# MainModule.net
KiCad netlist of a schematic drawn in EAGLE
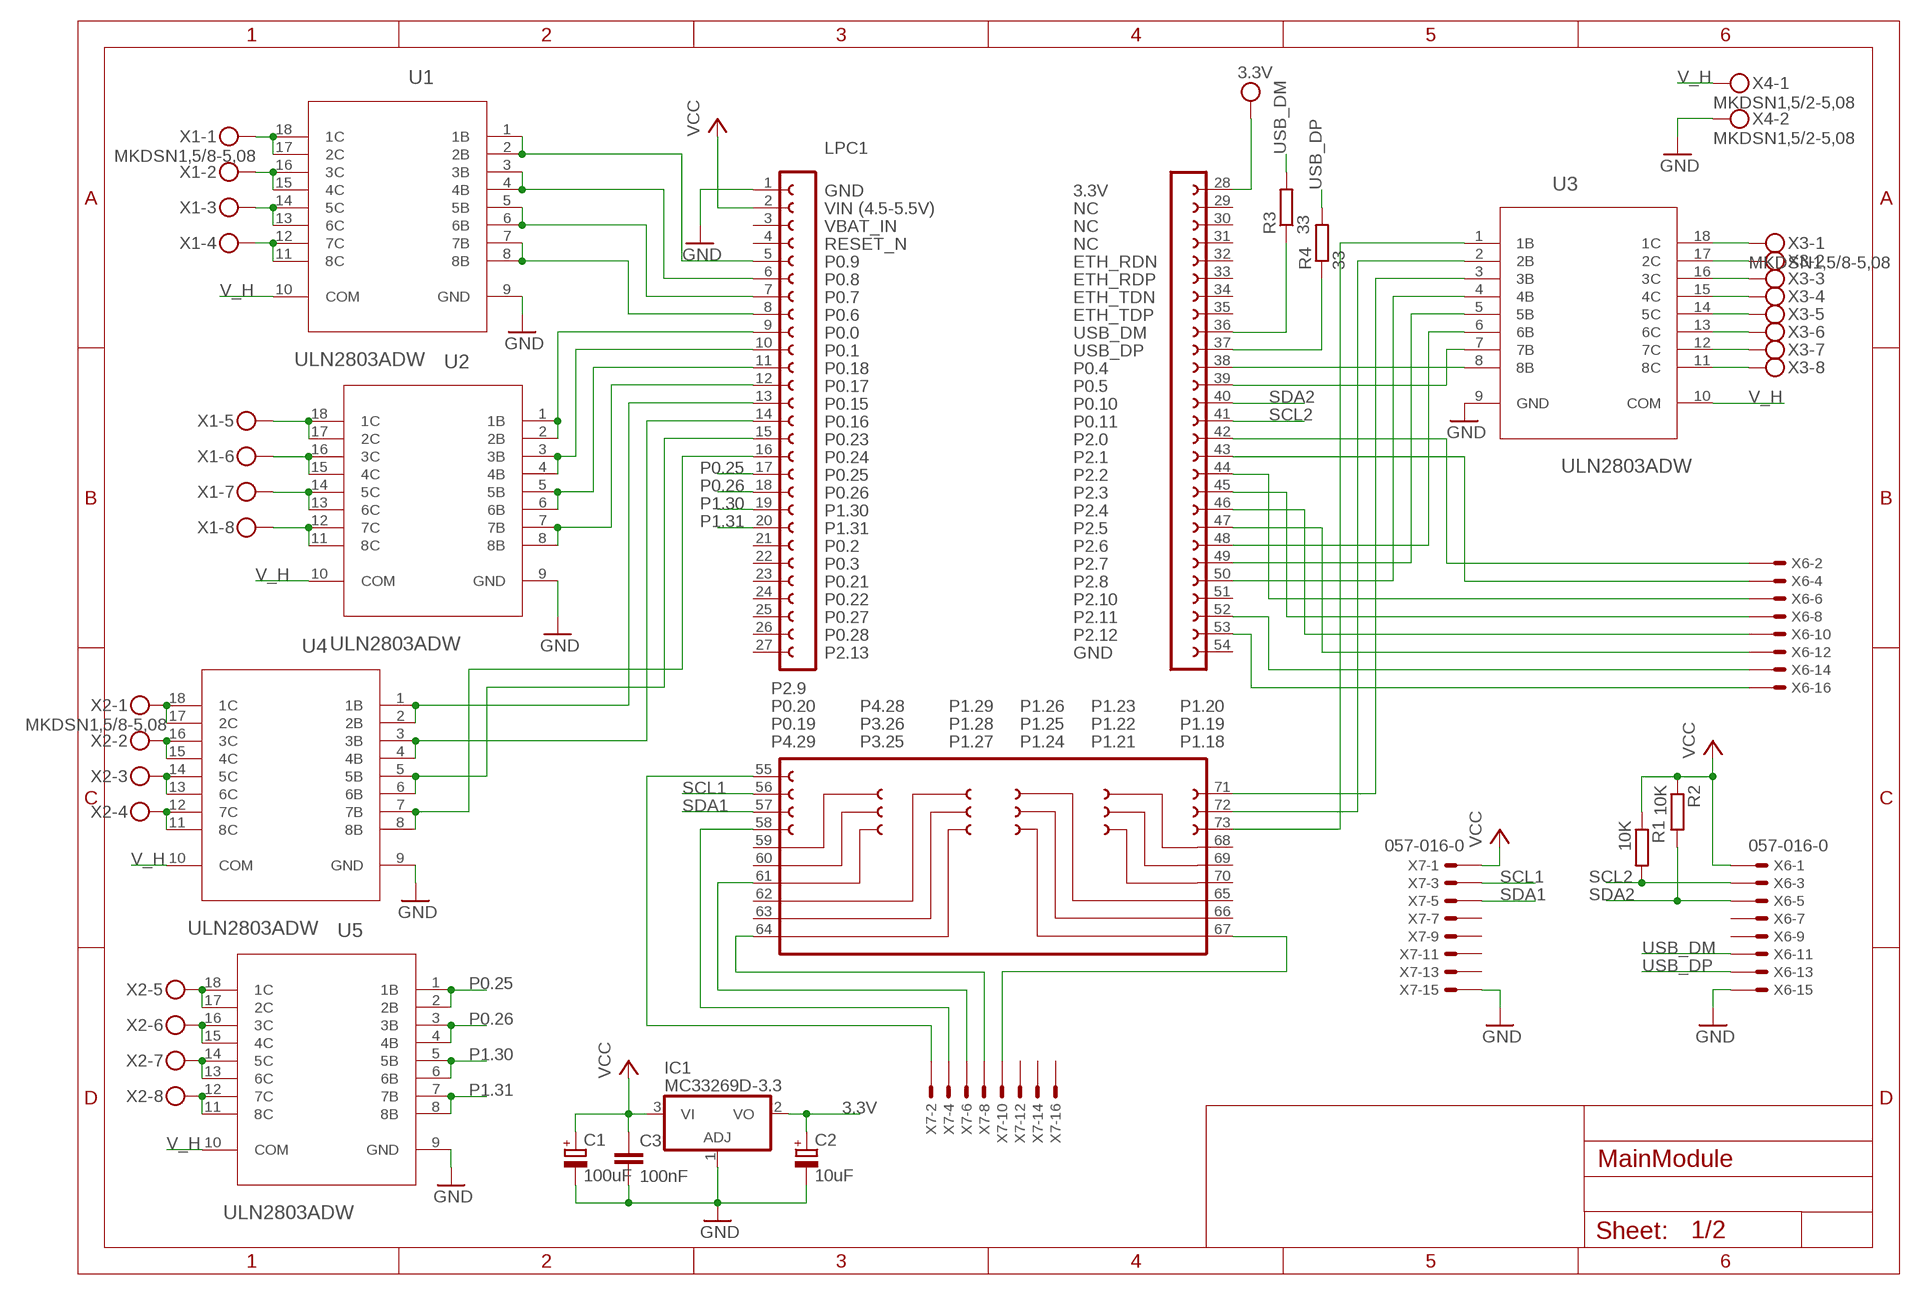
[diagram p0: schematic, sheet 1]
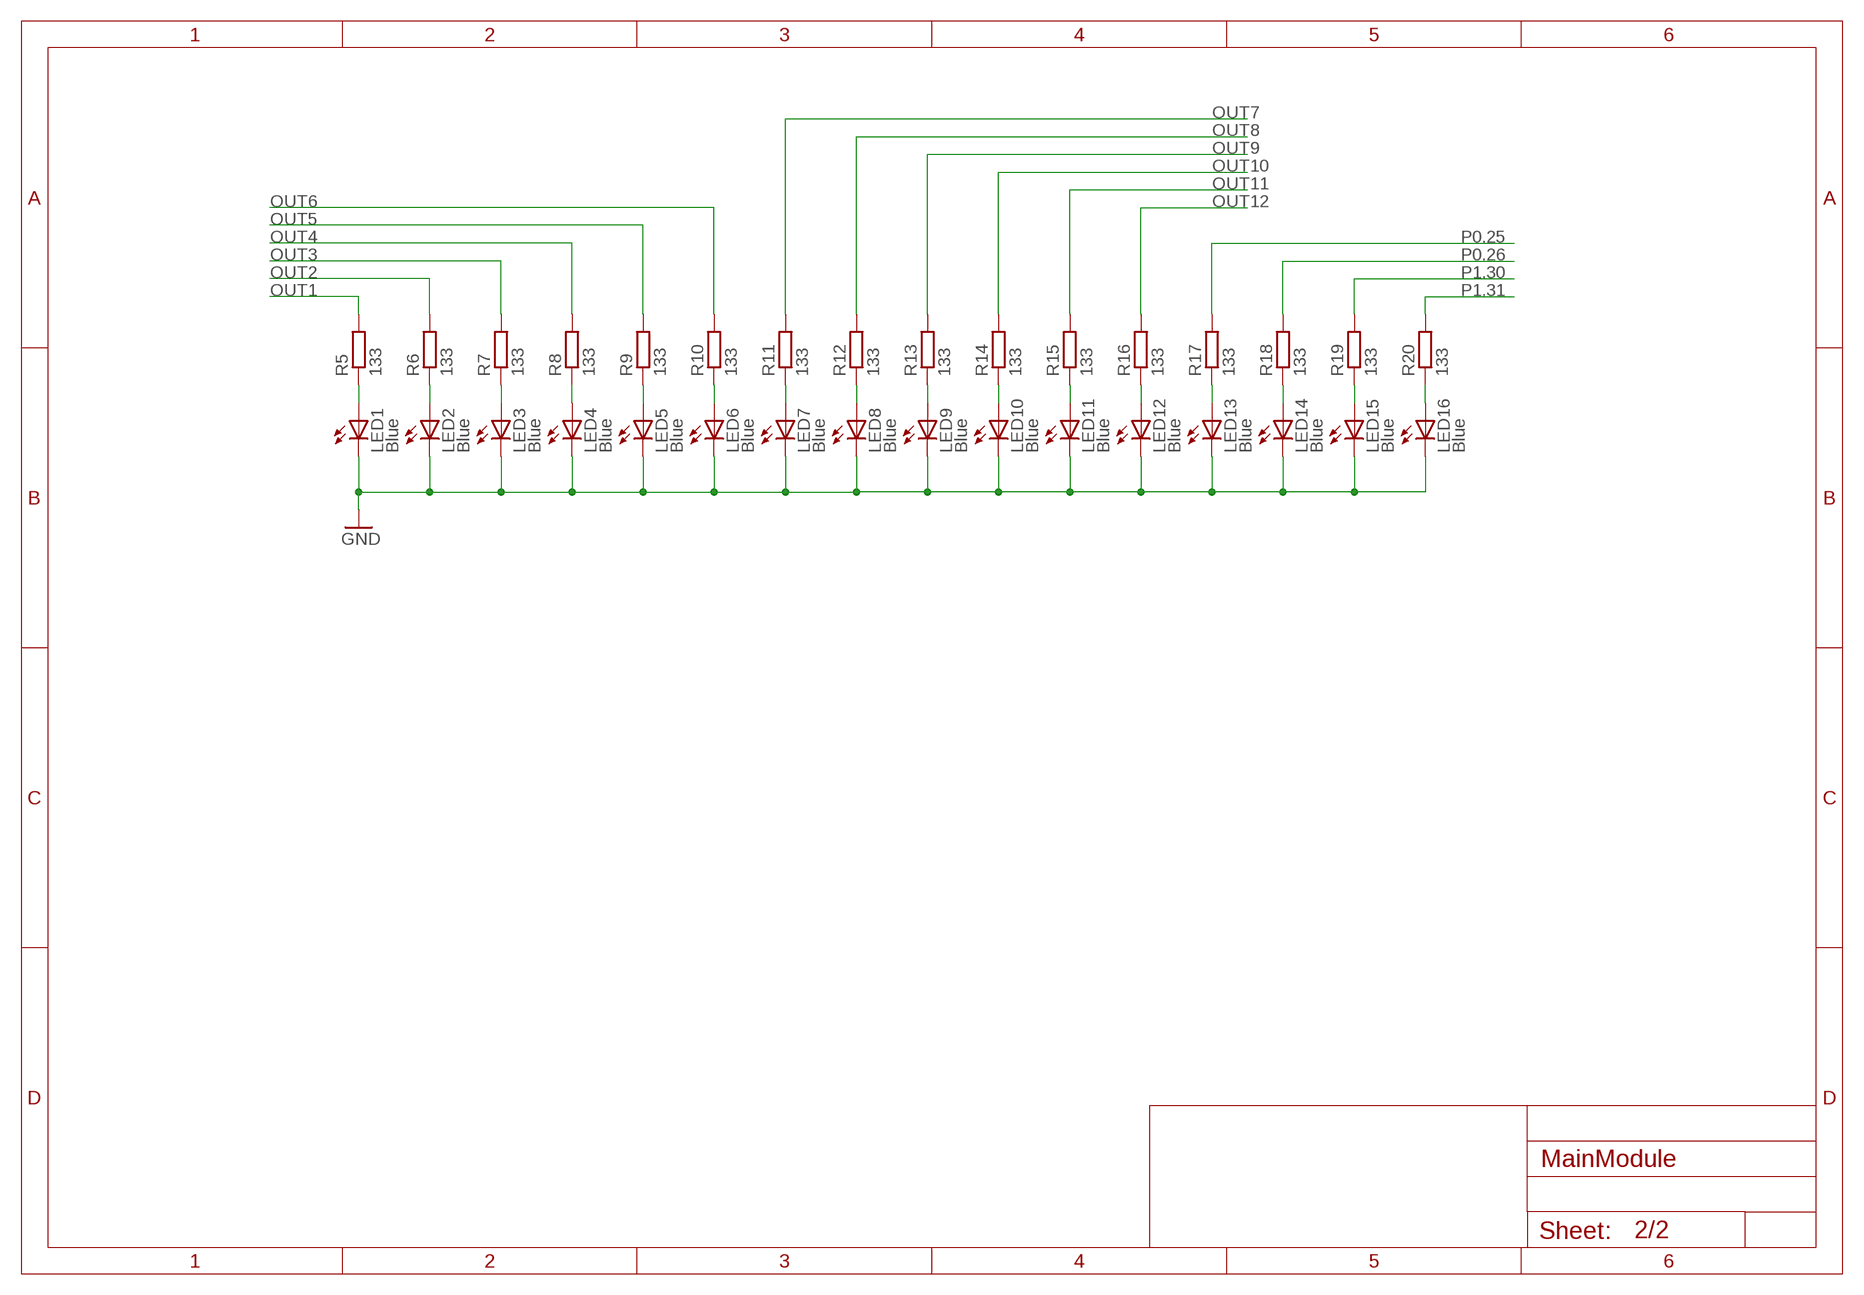
[diagram p1: schematic, sheet 2]

(export (version "E")
  (design (tool "Eeschema 10.0.6"))
  (components
    (comp (ref "C1")
      (value "100uF")
      (footprint "eagle-import:153CLV-0810")
      (libsource (lib "eagle-import") (part "CPOL-EU153CLV-0810"))
    )
    (comp (ref "C2")
      (value "10uF")
      (footprint "eagle-import:153CLV-0810")
      (libsource (lib "eagle-import") (part "CPOL-EU153CLV-0810"))
    )
    (comp (ref "C3")
      (value "100nF")
      (footprint "eagle-import:C0805")
      (libsource (lib "eagle-import") (part "C-EUC0805"))
    )
    (comp (ref "IC1")
      (value "MC33269D-3.3")
      (footprint "eagle-import:DPACK")
      (libsource (lib "eagle-import") (part "MC33269?D-3.3"))
    )
    (comp (ref "LPC1")
      (value "LPCXPRESSO_LPC1769")
      (footprint "eagle-import:LPCXPRESSO_LPC1769")
      (libsource (lib "eagle-import") (part "LPCXPRESSO_LPC1769"))
    )
    (comp (ref "R1")
      (value "10K")
      (footprint "eagle-import:MINI_MELF-0204W")
      (libsource (lib "eagle-import") (part "R-EU_MELF0204W"))
    )
    (comp (ref "R2")
      (value "10K")
      (footprint "eagle-import:MINI_MELF-0204W")
      (libsource (lib "eagle-import") (part "R-EU_MELF0204W"))
    )
    (comp (ref "R3")
      (value "33")
      (footprint "eagle-import:M3216")
      (libsource (lib "eagle-import") (part "resistor_R-EU_M3216"))
    )
    (comp (ref "R4")
      (value "33")
      (footprint "eagle-import:M3216")
      (libsource (lib "eagle-import") (part "resistor_R-EU_M3216"))
    )
    (comp (ref "U1")
      (value "ULN2803ADW")
      (footprint "eagle-import:SOIC127P1030X265-18N")
      (libsource (lib "eagle-import") (part "ULN2803ADW"))
    )
    (comp (ref "U2")
      (value "ULN2803ADW")
      (footprint "eagle-import:SOIC127P1030X265-18N")
      (libsource (lib "eagle-import") (part "ULN2803ADW"))
    )
    (comp (ref "U3")
      (value "ULN2803ADW")
      (footprint "eagle-import:SOIC127P1030X265-18N")
      (libsource (lib "eagle-import") (part "ULN2803ADW"))
    )
    (comp (ref "U4")
      (value "ULN2803ADW")
      (footprint "eagle-import:SOIC127P1030X265-18N")
      (libsource (lib "eagle-import") (part "ULN2803ADW"))
    )
    (comp (ref "U5")
      (value "ULN2803ADW")
      (footprint "eagle-import:SOIC127P1030X265-18N")
      (libsource (lib "eagle-import") (part "ULN2803ADW"))
    )
    (comp (ref "X1")
      (value "MKDSN1,5/8-5,08")
      (footprint "eagle-import:MKDSN1,5_8-5,08")
      (libsource (lib "eagle-import") (part "MKDSN1,5/8-5,08"))
    )
    (comp (ref "X2")
      (value "MKDSN1,5/8-5,08")
      (footprint "eagle-import:MKDSN1,5_8-5,08")
      (libsource (lib "eagle-import") (part "MKDSN1,5/8-5,08"))
    )
    (comp (ref "X3")
      (value "MKDSN1,5/8-5,08")
      (footprint "eagle-import:MKDSN1,5_8-5,08")
      (libsource (lib "eagle-import") (part "MKDSN1,5/8-5,08"))
    )
    (comp (ref "X4")
      (value "MKDSN1,5/2-5,08")
      (footprint "eagle-import:MKDSN1,5_2-5,08")
      (libsource (lib "eagle-import") (part "MKDSN1,5/2-5,08"))
    )
    (comp (ref "X6")
      (value "057-016-0")
      (footprint "eagle-import:057-016-0")
      (libsource (lib "eagle-import") (part "057-016-0"))
    )
    (comp (ref "X7")
      (value "057-016-0")
      (footprint "eagle-import:057-016-0")
      (libsource (lib "eagle-import") (part "057-016-0"))
    )
    (comp (ref "LED1")
      (value "Blue")
      (footprint "eagle-import:CHIPLED_0805")
      (libsource (lib "eagle-import") (part "LEDCHIPLED_0805"))
    )
    (comp (ref "LED2")
      (value "Blue")
      (footprint "eagle-import:CHIPLED_0805")
      (libsource (lib "eagle-import") (part "LEDCHIPLED_0805"))
    )
    (comp (ref "LED3")
      (value "Blue")
      (footprint "eagle-import:CHIPLED_0805")
      (libsource (lib "eagle-import") (part "LEDCHIPLED_0805"))
    )
    (comp (ref "LED4")
      (value "Blue")
      (footprint "eagle-import:CHIPLED_0805")
      (libsource (lib "eagle-import") (part "LEDCHIPLED_0805"))
    )
    (comp (ref "LED5")
      (value "Blue")
      (footprint "eagle-import:CHIPLED_0805")
      (libsource (lib "eagle-import") (part "LEDCHIPLED_0805"))
    )
    (comp (ref "LED6")
      (value "Blue")
      (footprint "eagle-import:CHIPLED_0805")
      (libsource (lib "eagle-import") (part "LEDCHIPLED_0805"))
    )
    (comp (ref "LED7")
      (value "Blue")
      (footprint "eagle-import:CHIPLED_0805")
      (libsource (lib "eagle-import") (part "LEDCHIPLED_0805"))
    )
    (comp (ref "LED8")
      (value "Blue")
      (footprint "eagle-import:CHIPLED_0805")
      (libsource (lib "eagle-import") (part "LEDCHIPLED_0805"))
    )
    (comp (ref "LED9")
      (value "Blue")
      (footprint "eagle-import:CHIPLED_0805")
      (libsource (lib "eagle-import") (part "LEDCHIPLED_0805"))
    )
    (comp (ref "LED10")
      (value "Blue")
      (footprint "eagle-import:CHIPLED_0805")
      (libsource (lib "eagle-import") (part "LEDCHIPLED_0805"))
    )
    (comp (ref "LED11")
      (value "Blue")
      (footprint "eagle-import:CHIPLED_0805")
      (libsource (lib "eagle-import") (part "LEDCHIPLED_0805"))
    )
    (comp (ref "LED12")
      (value "Blue")
      (footprint "eagle-import:CHIPLED_0805")
      (libsource (lib "eagle-import") (part "LEDCHIPLED_0805"))
    )
    (comp (ref "LED13")
      (value "Blue")
      (footprint "eagle-import:CHIPLED_0805")
      (libsource (lib "eagle-import") (part "LEDCHIPLED_0805"))
    )
    (comp (ref "LED14")
      (value "Blue")
      (footprint "eagle-import:CHIPLED_0805")
      (libsource (lib "eagle-import") (part "LEDCHIPLED_0805"))
    )
    (comp (ref "LED15")
      (value "Blue")
      (footprint "eagle-import:CHIPLED_0805")
      (libsource (lib "eagle-import") (part "LEDCHIPLED_0805"))
    )
    (comp (ref "LED16")
      (value "Blue")
      (footprint "eagle-import:CHIPLED_0805")
      (libsource (lib "eagle-import") (part "LEDCHIPLED_0805"))
    )
    (comp (ref "R5")
      (value "133")
      (footprint "eagle-import:R1206W")
      (libsource (lib "eagle-import") (part "R-EU_R1206W"))
    )
    (comp (ref "R6")
      (value "133")
      (footprint "eagle-import:R1206W")
      (libsource (lib "eagle-import") (part "R-EU_R1206W"))
    )
    (comp (ref "R7")
      (value "133")
      (footprint "eagle-import:R1206W")
      (libsource (lib "eagle-import") (part "R-EU_R1206W"))
    )
    (comp (ref "R8")
      (value "133")
      (footprint "eagle-import:R1206W")
      (libsource (lib "eagle-import") (part "R-EU_R1206W"))
    )
    (comp (ref "R9")
      (value "133")
      (footprint "eagle-import:R1206W")
      (libsource (lib "eagle-import") (part "R-EU_R1206W"))
    )
    (comp (ref "R10")
      (value "133")
      (footprint "eagle-import:R1206W")
      (libsource (lib "eagle-import") (part "R-EU_R1206W"))
    )
    (comp (ref "R11")
      (value "133")
      (footprint "eagle-import:R1206W")
      (libsource (lib "eagle-import") (part "R-EU_R1206W"))
    )
    (comp (ref "R12")
      (value "133")
      (footprint "eagle-import:R1206W")
      (libsource (lib "eagle-import") (part "R-EU_R1206W"))
    )
    (comp (ref "R13")
      (value "133")
      (footprint "eagle-import:R1206W")
      (libsource (lib "eagle-import") (part "R-EU_R1206W"))
    )
    (comp (ref "R14")
      (value "133")
      (footprint "eagle-import:R1206W")
      (libsource (lib "eagle-import") (part "R-EU_R1206W"))
    )
    (comp (ref "R15")
      (value "133")
      (footprint "eagle-import:R1206W")
      (libsource (lib "eagle-import") (part "R-EU_R1206W"))
    )
    (comp (ref "R16")
      (value "133")
      (footprint "eagle-import:R1206W")
      (libsource (lib "eagle-import") (part "R-EU_R1206W"))
    )
    (comp (ref "R17")
      (value "133")
      (footprint "eagle-import:R1206W")
      (libsource (lib "eagle-import") (part "R-EU_R1206W"))
    )
    (comp (ref "R18")
      (value "133")
      (footprint "eagle-import:R1206W")
      (libsource (lib "eagle-import") (part "R-EU_R1206W"))
    )
    (comp (ref "R19")
      (value "133")
      (footprint "eagle-import:R1206W")
      (libsource (lib "eagle-import") (part "R-EU_R1206W"))
    )
    (comp (ref "R20")
      (value "133")
      (footprint "eagle-import:R1206W")
      (libsource (lib "eagle-import") (part "R-EU_R1206W"))
    )
  )
  (nets
    (net (code "1") (name "3.3V") (class "Default")
      (node (ref "C2") (pin "+") (pinfunction "+_+") (pintype "passive"))
      (node (ref "IC1") (pin "2") (pinfunction "VO_2") (pintype "passive"))
      (node (ref "LPC1") (pin "28") (pinfunction "28_28") (pintype "passive"))
    )
    (net (code "2") (name "GND") (class "Default")
      (node (ref "C1") (pin "-") (pinfunction "-_-") (pintype "passive"))
      (node (ref "C2") (pin "-") (pinfunction "-_-") (pintype "passive"))
      (node (ref "C3") (pin "2") (pinfunction "2_2") (pintype "passive"))
      (node (ref "IC1") (pin "1") (pinfunction "ADJ_1") (pintype "input"))
      (node (ref "LED1") (pin "C") (pinfunction "C_C") (pintype "passive"))
      (node (ref "LED10") (pin "C") (pinfunction "C_C") (pintype "passive"))
      (node (ref "LED11") (pin "C") (pinfunction "C_C") (pintype "passive"))
      (node (ref "LED12") (pin "C") (pinfunction "C_C") (pintype "passive"))
      (node (ref "LED13") (pin "C") (pinfunction "C_C") (pintype "passive"))
      (node (ref "LED14") (pin "C") (pinfunction "C_C") (pintype "passive"))
      (node (ref "LED15") (pin "C") (pinfunction "C_C") (pintype "passive"))
      (node (ref "LED16") (pin "C") (pinfunction "C_C") (pintype "passive"))
      (node (ref "LED2") (pin "C") (pinfunction "C_C") (pintype "passive"))
      (node (ref "LED3") (pin "C") (pinfunction "C_C") (pintype "passive"))
      (node (ref "LED4") (pin "C") (pinfunction "C_C") (pintype "passive"))
      (node (ref "LED5") (pin "C") (pinfunction "C_C") (pintype "passive"))
      (node (ref "LED6") (pin "C") (pinfunction "C_C") (pintype "passive"))
      (node (ref "LED7") (pin "C") (pinfunction "C_C") (pintype "passive"))
      (node (ref "LED8") (pin "C") (pinfunction "C_C") (pintype "passive"))
      (node (ref "LED9") (pin "C") (pinfunction "C_C") (pintype "passive"))
      (node (ref "LPC1") (pin "1") (pinfunction "1_1") (pintype "passive"))
      (node (ref "U1") (pin "9") (pinfunction "GND_9") (pintype "passive"))
      (node (ref "U2") (pin "9") (pinfunction "GND_9") (pintype "passive"))
      (node (ref "U3") (pin "9") (pinfunction "GND_9") (pintype "passive"))
      (node (ref "U4") (pin "9") (pinfunction "GND_9") (pintype "passive"))
      (node (ref "U5") (pin "9") (pinfunction "GND_9") (pintype "passive"))
      (node (ref "X4") (pin "2") (pinfunction "KL_2") (pintype "passive"))
      (node (ref "X6") (pin "15") (pinfunction "S_15") (pintype "passive"))
      (node (ref "X7") (pin "15") (pinfunction "S_15") (pintype "passive"))
    )
    (net (code "3") (name "Net-(LED1-PadA)") (class "Default")
      (node (ref "LED1") (pin "A") (pinfunction "A_A") (pintype "passive"))
      (node (ref "R5") (pin "1") (pinfunction "1_1") (pintype "passive"))
    )
    (net (code "4") (name "Net-(LED2-PadA)") (class "Default")
      (node (ref "LED2") (pin "A") (pinfunction "A_A") (pintype "passive"))
      (node (ref "R6") (pin "1") (pinfunction "1_1") (pintype "passive"))
    )
    (net (code "5") (name "Net-(LED3-PadA)") (class "Default")
      (node (ref "LED3") (pin "A") (pinfunction "A_A") (pintype "passive"))
      (node (ref "R7") (pin "1") (pinfunction "1_1") (pintype "passive"))
    )
    (net (code "6") (name "Net-(LED4-PadA)") (class "Default")
      (node (ref "LED4") (pin "A") (pinfunction "A_A") (pintype "passive"))
      (node (ref "R8") (pin "1") (pinfunction "1_1") (pintype "passive"))
    )
    (net (code "7") (name "Net-(LED5-PadA)") (class "Default")
      (node (ref "LED5") (pin "A") (pinfunction "A_A") (pintype "passive"))
      (node (ref "R9") (pin "1") (pinfunction "1_1") (pintype "passive"))
    )
    (net (code "8") (name "Net-(LED6-PadA)") (class "Default")
      (node (ref "LED6") (pin "A") (pinfunction "A_A") (pintype "passive"))
      (node (ref "R10") (pin "1") (pinfunction "1_1") (pintype "passive"))
    )
    (net (code "9") (name "Net-(LED7-PadA)") (class "Default")
      (node (ref "LED7") (pin "A") (pinfunction "A_A") (pintype "passive"))
      (node (ref "R11") (pin "1") (pinfunction "1_1") (pintype "passive"))
    )
    (net (code "10") (name "Net-(LED8-PadA)") (class "Default")
      (node (ref "LED8") (pin "A") (pinfunction "A_A") (pintype "passive"))
      (node (ref "R12") (pin "1") (pinfunction "1_1") (pintype "passive"))
    )
    (net (code "11") (name "Net-(LED9-PadA)") (class "Default")
      (node (ref "LED9") (pin "A") (pinfunction "A_A") (pintype "passive"))
      (node (ref "R13") (pin "1") (pinfunction "1_1") (pintype "passive"))
    )
    (net (code "12") (name "Net-(LED10-PadA)") (class "Default")
      (node (ref "LED10") (pin "A") (pinfunction "A_A") (pintype "passive"))
      (node (ref "R14") (pin "1") (pinfunction "1_1") (pintype "passive"))
    )
    (net (code "13") (name "Net-(LED11-PadA)") (class "Default")
      (node (ref "LED11") (pin "A") (pinfunction "A_A") (pintype "passive"))
      (node (ref "R15") (pin "1") (pinfunction "1_1") (pintype "passive"))
    )
    (net (code "14") (name "Net-(LED12-PadA)") (class "Default")
      (node (ref "LED12") (pin "A") (pinfunction "A_A") (pintype "passive"))
      (node (ref "R16") (pin "1") (pinfunction "1_1") (pintype "passive"))
    )
    (net (code "15") (name "Net-(LED13-PadA)") (class "Default")
      (node (ref "LED13") (pin "A") (pinfunction "A_A") (pintype "passive"))
      (node (ref "R17") (pin "1") (pinfunction "1_1") (pintype "passive"))
    )
    (net (code "16") (name "Net-(LED14-PadA)") (class "Default")
      (node (ref "LED14") (pin "A") (pinfunction "A_A") (pintype "passive"))
      (node (ref "R18") (pin "1") (pinfunction "1_1") (pintype "passive"))
    )
    (net (code "17") (name "Net-(LED15-PadA)") (class "Default")
      (node (ref "LED15") (pin "A") (pinfunction "A_A") (pintype "passive"))
      (node (ref "R19") (pin "1") (pinfunction "1_1") (pintype "passive"))
    )
    (net (code "18") (name "Net-(LED16-PadA)") (class "Default")
      (node (ref "LED16") (pin "A") (pinfunction "A_A") (pintype "passive"))
      (node (ref "R20") (pin "1") (pinfunction "1_1") (pintype "passive"))
    )
    (net (code "19") (name "Net-(LPC1-Pad36)") (class "Default")
      (node (ref "LPC1") (pin "36") (pinfunction "36_36") (pintype "passive"))
      (node (ref "R3") (pin "1") (pinfunction "1_1") (pintype "passive"))
    )
    (net (code "20") (name "Net-(LPC1-Pad37)") (class "Default")
      (node (ref "LPC1") (pin "37") (pinfunction "37_37") (pintype "passive"))
      (node (ref "R4") (pin "1") (pinfunction "1_1") (pintype "passive"))
    )
    (net (code "21") (name "Net-(U1-1C)") (class "Default")
      (node (ref "U1") (pin "17") (pinfunction "2C_17") (pintype "output"))
      (node (ref "U1") (pin "18") (pinfunction "1C_18") (pintype "output"))
      (node (ref "X1") (pin "1") (pinfunction "KL_1") (pintype "passive"))
    )
    (net (code "22") (name "Net-(U1-3C)") (class "Default")
      (node (ref "U1") (pin "15") (pinfunction "4C_15") (pintype "output"))
      (node (ref "U1") (pin "16") (pinfunction "3C_16") (pintype "output"))
      (node (ref "X1") (pin "2") (pinfunction "KL_2") (pintype "passive"))
    )
    (net (code "23") (name "Net-(U1-5C)") (class "Default")
      (node (ref "U1") (pin "13") (pinfunction "6C_13") (pintype "output"))
      (node (ref "U1") (pin "14") (pinfunction "5C_14") (pintype "output"))
      (node (ref "X1") (pin "3") (pinfunction "KL_3") (pintype "passive"))
    )
    (net (code "24") (name "Net-(U1-7C)") (class "Default")
      (node (ref "U1") (pin "11") (pinfunction "8C_11") (pintype "output"))
      (node (ref "U1") (pin "12") (pinfunction "7C_12") (pintype "output"))
      (node (ref "X1") (pin "4") (pinfunction "KL_4") (pintype "passive"))
    )
    (net (code "25") (name "Net-(U2-1C)") (class "Default")
      (node (ref "U2") (pin "17") (pinfunction "2C_17") (pintype "output"))
      (node (ref "U2") (pin "18") (pinfunction "1C_18") (pintype "output"))
      (node (ref "X1") (pin "5") (pinfunction "KL_5") (pintype "passive"))
    )
    (net (code "26") (name "Net-(U2-3C)") (class "Default")
      (node (ref "U2") (pin "15") (pinfunction "4C_15") (pintype "output"))
      (node (ref "U2") (pin "16") (pinfunction "3C_16") (pintype "output"))
      (node (ref "X1") (pin "6") (pinfunction "KL_6") (pintype "passive"))
    )
    (net (code "27") (name "Net-(U2-5C)") (class "Default")
      (node (ref "U2") (pin "13") (pinfunction "6C_13") (pintype "output"))
      (node (ref "U2") (pin "14") (pinfunction "5C_14") (pintype "output"))
      (node (ref "X1") (pin "7") (pinfunction "KL_7") (pintype "passive"))
    )
    (net (code "28") (name "Net-(U2-7C)") (class "Default")
      (node (ref "U2") (pin "11") (pinfunction "8C_11") (pintype "output"))
      (node (ref "U2") (pin "12") (pinfunction "7C_12") (pintype "output"))
      (node (ref "X1") (pin "8") (pinfunction "KL_8") (pintype "passive"))
    )
    (net (code "29") (name "Net-(U3-1B)") (class "Default")
      (node (ref "LPC1") (pin "73") (pinfunction "73_73") (pintype "passive"))
      (node (ref "U3") (pin "1") (pinfunction "1B_1") (pintype "input"))
    )
    (net (code "30") (name "Net-(U3-1C)") (class "Default")
      (node (ref "U3") (pin "18") (pinfunction "1C_18") (pintype "output"))
      (node (ref "X3") (pin "1") (pinfunction "KL_1") (pintype "passive"))
    )
    (net (code "31") (name "Net-(U3-2B)") (class "Default")
      (node (ref "LPC1") (pin "72") (pinfunction "72_72") (pintype "passive"))
      (node (ref "U3") (pin "2") (pinfunction "2B_2") (pintype "input"))
    )
    (net (code "32") (name "Net-(U3-2C)") (class "Default")
      (node (ref "U3") (pin "17") (pinfunction "2C_17") (pintype "output"))
      (node (ref "X3") (pin "2") (pinfunction "KL_2") (pintype "passive"))
    )
    (net (code "33") (name "Net-(U3-3B)") (class "Default")
      (node (ref "LPC1") (pin "71") (pinfunction "71_71") (pintype "passive"))
      (node (ref "U3") (pin "3") (pinfunction "3B_3") (pintype "input"))
    )
    (net (code "34") (name "Net-(U3-3C)") (class "Default")
      (node (ref "U3") (pin "16") (pinfunction "3C_16") (pintype "output"))
      (node (ref "X3") (pin "3") (pinfunction "KL_3") (pintype "passive"))
    )
    (net (code "35") (name "Net-(U3-4B)") (class "Default")
      (node (ref "LPC1") (pin "50") (pinfunction "50_50") (pintype "passive"))
      (node (ref "U3") (pin "4") (pinfunction "4B_4") (pintype "input"))
    )
    (net (code "36") (name "Net-(U3-4C)") (class "Default")
      (node (ref "U3") (pin "15") (pinfunction "4C_15") (pintype "output"))
      (node (ref "X3") (pin "4") (pinfunction "KL_4") (pintype "passive"))
    )
    (net (code "37") (name "Net-(U3-5B)") (class "Default")
      (node (ref "LPC1") (pin "49") (pinfunction "49_49") (pintype "passive"))
      (node (ref "U3") (pin "5") (pinfunction "5B_5") (pintype "input"))
    )
    (net (code "38") (name "Net-(U3-5C)") (class "Default")
      (node (ref "U3") (pin "14") (pinfunction "5C_14") (pintype "output"))
      (node (ref "X3") (pin "5") (pinfunction "KL_5") (pintype "passive"))
    )
    (net (code "39") (name "Net-(U3-6B)") (class "Default")
      (node (ref "LPC1") (pin "48") (pinfunction "48_48") (pintype "passive"))
      (node (ref "U3") (pin "6") (pinfunction "6B_6") (pintype "input"))
    )
    (net (code "40") (name "Net-(U3-6C)") (class "Default")
      (node (ref "U3") (pin "13") (pinfunction "6C_13") (pintype "output"))
      (node (ref "X3") (pin "6") (pinfunction "KL_6") (pintype "passive"))
    )
    (net (code "41") (name "Net-(U3-7B)") (class "Default")
      (node (ref "LPC1") (pin "39") (pinfunction "39_39") (pintype "passive"))
      (node (ref "U3") (pin "7") (pinfunction "7B_7") (pintype "input"))
    )
    (net (code "42") (name "Net-(U3-7C)") (class "Default")
      (node (ref "U3") (pin "12") (pinfunction "7C_12") (pintype "output"))
      (node (ref "X3") (pin "7") (pinfunction "KL_7") (pintype "passive"))
    )
    (net (code "43") (name "Net-(U3-8B)") (class "Default")
      (node (ref "LPC1") (pin "38") (pinfunction "38_38") (pintype "passive"))
      (node (ref "U3") (pin "8") (pinfunction "8B_8") (pintype "input"))
    )
    (net (code "44") (name "Net-(U3-8C)") (class "Default")
      (node (ref "U3") (pin "11") (pinfunction "8C_11") (pintype "output"))
      (node (ref "X3") (pin "8") (pinfunction "KL_8") (pintype "passive"))
    )
    (net (code "45") (name "Net-(U4-1C)") (class "Default")
      (node (ref "U4") (pin "17") (pinfunction "2C_17") (pintype "output"))
      (node (ref "U4") (pin "18") (pinfunction "1C_18") (pintype "output"))
      (node (ref "X2") (pin "1") (pinfunction "KL_1") (pintype "passive"))
    )
    (net (code "46") (name "Net-(U4-3C)") (class "Default")
      (node (ref "U4") (pin "15") (pinfunction "4C_15") (pintype "output"))
      (node (ref "U4") (pin "16") (pinfunction "3C_16") (pintype "output"))
      (node (ref "X2") (pin "2") (pinfunction "KL_2") (pintype "passive"))
    )
    (net (code "47") (name "Net-(U4-5C)") (class "Default")
      (node (ref "U4") (pin "13") (pinfunction "6C_13") (pintype "output"))
      (node (ref "U4") (pin "14") (pinfunction "5C_14") (pintype "output"))
      (node (ref "X2") (pin "3") (pinfunction "KL_3") (pintype "passive"))
    )
    (net (code "48") (name "Net-(U4-7C)") (class "Default")
      (node (ref "U4") (pin "11") (pinfunction "8C_11") (pintype "output"))
      (node (ref "U4") (pin "12") (pinfunction "7C_12") (pintype "output"))
      (node (ref "X2") (pin "4") (pinfunction "KL_4") (pintype "passive"))
    )
    (net (code "49") (name "Net-(U5-1C)") (class "Default")
      (node (ref "U5") (pin "17") (pinfunction "2C_17") (pintype "output"))
      (node (ref "U5") (pin "18") (pinfunction "1C_18") (pintype "output"))
      (node (ref "X2") (pin "5") (pinfunction "KL_5") (pintype "passive"))
    )
    (net (code "50") (name "Net-(U5-3C)") (class "Default")
      (node (ref "U5") (pin "15") (pinfunction "4C_15") (pintype "output"))
      (node (ref "U5") (pin "16") (pinfunction "3C_16") (pintype "output"))
      (node (ref "X2") (pin "6") (pinfunction "KL_6") (pintype "passive"))
    )
    (net (code "51") (name "Net-(U5-5C)") (class "Default")
      (node (ref "U5") (pin "13") (pinfunction "6C_13") (pintype "output"))
      (node (ref "U5") (pin "14") (pinfunction "5C_14") (pintype "output"))
      (node (ref "X2") (pin "7") (pinfunction "KL_7") (pintype "passive"))
    )
    (net (code "52") (name "Net-(U5-7C)") (class "Default")
      (node (ref "U5") (pin "11") (pinfunction "8C_11") (pintype "output"))
      (node (ref "U5") (pin "12") (pinfunction "7C_12") (pintype "output"))
      (node (ref "X2") (pin "8") (pinfunction "KL_8") (pintype "passive"))
    )
    (net (code "53") (name "Net-(X6B-S)") (class "Default")
      (node (ref "LPC1") (pin "46") (pinfunction "46_46") (pintype "passive"))
      (node (ref "X6") (pin "10") (pinfunction "S_10") (pintype "passive"))
    )
    (net (code "54") (name "Net-(X6D-S)") (class "Default")
      (node (ref "LPC1") (pin "47") (pinfunction "47_47") (pintype "passive"))
      (node (ref "X6") (pin "12") (pinfunction "S_12") (pintype "passive"))
    )
    (net (code "55") (name "Net-(X6F-S)") (class "Default")
      (node (ref "LPC1") (pin "52") (pinfunction "52_52") (pintype "passive"))
      (node (ref "X6") (pin "14") (pinfunction "S_14") (pintype "passive"))
    )
    (net (code "56") (name "Net-(X6H-S)") (class "Default")
      (node (ref "LPC1") (pin "53") (pinfunction "53_53") (pintype "passive"))
      (node (ref "X6") (pin "16") (pinfunction "S_16") (pintype "passive"))
    )
    (net (code "57") (name "Net-(X6I-S)") (class "Default")
      (node (ref "LPC1") (pin "42") (pinfunction "42_42") (pintype "passive"))
      (node (ref "X6") (pin "2") (pinfunction "S_2") (pintype "passive"))
    )
    (net (code "58") (name "Net-(X6K-S)") (class "Default")
      (node (ref "LPC1") (pin "43") (pinfunction "43_43") (pintype "passive"))
      (node (ref "X6") (pin "4") (pinfunction "S_4") (pintype "passive"))
    )
    (net (code "59") (name "Net-(X6M-S)") (class "Default")
      (node (ref "LPC1") (pin "44") (pinfunction "44_44") (pintype "passive"))
      (node (ref "X6") (pin "6") (pinfunction "S_6") (pintype "passive"))
    )
    (net (code "60") (name "Net-(X6O-S)") (class "Default")
      (node (ref "LPC1") (pin "45") (pinfunction "45_45") (pintype "passive"))
      (node (ref "X6") (pin "8") (pinfunction "S_8") (pintype "passive"))
    )
    (net (code "61") (name "Net-(X7B-S)") (class "Default")
      (node (ref "LPC1") (pin "67") (pinfunction "67_67") (pintype "passive"))
      (node (ref "X7") (pin "10") (pinfunction "S_10") (pintype "passive"))
    )
    (net (code "62") (name "Net-(X7I-S)") (class "Default")
      (node (ref "LPC1") (pin "55") (pinfunction "55_55") (pintype "passive"))
      (node (ref "X7") (pin "2") (pinfunction "S_2") (pintype "passive"))
    )
    (net (code "63") (name "Net-(X7K-S)") (class "Default")
      (node (ref "LPC1") (pin "58") (pinfunction "58_58") (pintype "passive"))
      (node (ref "X7") (pin "4") (pinfunction "S_4") (pintype "passive"))
    )
    (net (code "64") (name "Net-(X7M-S)") (class "Default")
      (node (ref "LPC1") (pin "61") (pinfunction "61_61") (pintype "passive"))
      (node (ref "X7") (pin "6") (pinfunction "S_6") (pintype "passive"))
    )
    (net (code "65") (name "Net-(X7O-S)") (class "Default")
      (node (ref "LPC1") (pin "64") (pinfunction "64_64") (pintype "passive"))
      (node (ref "X7") (pin "8") (pinfunction "S_8") (pintype "passive"))
    )
    (net (code "66") (name "OUT1") (class "Default")
      (node (ref "LPC1") (pin "5") (pinfunction "5_5") (pintype "passive"))
      (node (ref "R5") (pin "2") (pinfunction "2_2") (pintype "passive"))
      (node (ref "U1") (pin "1") (pinfunction "1B_1") (pintype "input"))
      (node (ref "U1") (pin "2") (pinfunction "2B_2") (pintype "input"))
    )
    (net (code "67") (name "OUT2") (class "Default")
      (node (ref "LPC1") (pin "6") (pinfunction "6_6") (pintype "passive"))
      (node (ref "R6") (pin "2") (pinfunction "2_2") (pintype "passive"))
      (node (ref "U1") (pin "3") (pinfunction "3B_3") (pintype "input"))
      (node (ref "U1") (pin "4") (pinfunction "4B_4") (pintype "input"))
    )
    (net (code "68") (name "OUT3") (class "Default")
      (node (ref "LPC1") (pin "7") (pinfunction "7_7") (pintype "passive"))
      (node (ref "R7") (pin "2") (pinfunction "2_2") (pintype "passive"))
      (node (ref "U1") (pin "5") (pinfunction "5B_5") (pintype "input"))
      (node (ref "U1") (pin "6") (pinfunction "6B_6") (pintype "input"))
    )
    (net (code "69") (name "OUT4") (class "Default")
      (node (ref "LPC1") (pin "8") (pinfunction "8_8") (pintype "passive"))
      (node (ref "R8") (pin "2") (pinfunction "2_2") (pintype "passive"))
      (node (ref "U1") (pin "7") (pinfunction "7B_7") (pintype "input"))
      (node (ref "U1") (pin "8") (pinfunction "8B_8") (pintype "input"))
    )
    (net (code "70") (name "OUT5") (class "Default")
      (node (ref "LPC1") (pin "9") (pinfunction "9_9") (pintype "passive"))
      (node (ref "R9") (pin "2") (pinfunction "2_2") (pintype "passive"))
      (node (ref "U2") (pin "1") (pinfunction "1B_1") (pintype "input"))
      (node (ref "U2") (pin "2") (pinfunction "2B_2") (pintype "input"))
    )
    (net (code "71") (name "OUT6") (class "Default")
      (node (ref "LPC1") (pin "10") (pinfunction "10_10") (pintype "passive"))
      (node (ref "R10") (pin "2") (pinfunction "2_2") (pintype "passive"))
      (node (ref "U2") (pin "3") (pinfunction "3B_3") (pintype "input"))
      (node (ref "U2") (pin "4") (pinfunction "4B_4") (pintype "input"))
    )
    (net (code "72") (name "OUT7") (class "Default")
      (node (ref "LPC1") (pin "11") (pinfunction "11_11") (pintype "passive"))
      (node (ref "R11") (pin "2") (pinfunction "2_2") (pintype "passive"))
      (node (ref "U2") (pin "5") (pinfunction "5B_5") (pintype "input"))
      (node (ref "U2") (pin "6") (pinfunction "6B_6") (pintype "input"))
    )
    (net (code "73") (name "OUT8") (class "Default")
      (node (ref "LPC1") (pin "12") (pinfunction "12_12") (pintype "passive"))
      (node (ref "R12") (pin "2") (pinfunction "2_2") (pintype "passive"))
      (node (ref "U2") (pin "7") (pinfunction "7B_7") (pintype "input"))
      (node (ref "U2") (pin "8") (pinfunction "8B_8") (pintype "input"))
    )
    (net (code "74") (name "OUT9") (class "Default")
      (node (ref "LPC1") (pin "13") (pinfunction "13_13") (pintype "passive"))
      (node (ref "R13") (pin "2") (pinfunction "2_2") (pintype "passive"))
      (node (ref "U4") (pin "1") (pinfunction "1B_1") (pintype "input"))
      (node (ref "U4") (pin "2") (pinfunction "2B_2") (pintype "input"))
    )
    (net (code "75") (name "OUT10") (class "Default")
      (node (ref "LPC1") (pin "14") (pinfunction "14_14") (pintype "passive"))
      (node (ref "R14") (pin "2") (pinfunction "2_2") (pintype "passive"))
      (node (ref "U4") (pin "3") (pinfunction "3B_3") (pintype "input"))
      (node (ref "U4") (pin "4") (pinfunction "4B_4") (pintype "input"))
    )
    (net (code "76") (name "OUT11") (class "Default")
      (node (ref "LPC1") (pin "15") (pinfunction "15_15") (pintype "passive"))
      (node (ref "R15") (pin "2") (pinfunction "2_2") (pintype "passive"))
      (node (ref "U4") (pin "5") (pinfunction "5B_5") (pintype "input"))
      (node (ref "U4") (pin "6") (pinfunction "6B_6") (pintype "input"))
    )
    (net (code "77") (name "OUT12") (class "Default")
      (node (ref "LPC1") (pin "16") (pinfunction "16_16") (pintype "passive"))
      (node (ref "R16") (pin "2") (pinfunction "2_2") (pintype "passive"))
      (node (ref "U4") (pin "7") (pinfunction "7B_7") (pintype "input"))
      (node (ref "U4") (pin "8") (pinfunction "8B_8") (pintype "input"))
    )
    (net (code "78") (name "P0.25") (class "Default")
      (node (ref "LPC1") (pin "17") (pinfunction "17_17") (pintype "passive"))
      (node (ref "R17") (pin "2") (pinfunction "2_2") (pintype "passive"))
      (node (ref "U5") (pin "1") (pinfunction "1B_1") (pintype "input"))
      (node (ref "U5") (pin "2") (pinfunction "2B_2") (pintype "input"))
    )
    (net (code "79") (name "P0.26") (class "Default")
      (node (ref "LPC1") (pin "18") (pinfunction "18_18") (pintype "passive"))
      (node (ref "R18") (pin "2") (pinfunction "2_2") (pintype "passive"))
      (node (ref "U5") (pin "3") (pinfunction "3B_3") (pintype "input"))
      (node (ref "U5") (pin "4") (pinfunction "4B_4") (pintype "input"))
    )
    (net (code "80") (name "P1.30") (class "Default")
      (node (ref "LPC1") (pin "19") (pinfunction "19_19") (pintype "passive"))
      (node (ref "R19") (pin "2") (pinfunction "2_2") (pintype "passive"))
      (node (ref "U5") (pin "5") (pinfunction "5B_5") (pintype "input"))
      (node (ref "U5") (pin "6") (pinfunction "6B_6") (pintype "input"))
    )
    (net (code "81") (name "P1.31") (class "Default")
      (node (ref "LPC1") (pin "20") (pinfunction "20_20") (pintype "passive"))
      (node (ref "R20") (pin "2") (pinfunction "2_2") (pintype "passive"))
      (node (ref "U5") (pin "7") (pinfunction "7B_7") (pintype "input"))
      (node (ref "U5") (pin "8") (pinfunction "8B_8") (pintype "input"))
    )
    (net (code "82") (name "SCL1") (class "Default")
      (node (ref "LPC1") (pin "56") (pinfunction "56_56") (pintype "passive"))
      (node (ref "X7") (pin "3") (pinfunction "S_3") (pintype "passive"))
    )
    (net (code "83") (name "SCL2") (class "Default")
      (node (ref "LPC1") (pin "41") (pinfunction "41_41") (pintype "passive"))
      (node (ref "R1") (pin "2") (pinfunction "2_2") (pintype "passive"))
      (node (ref "X6") (pin "3") (pinfunction "S_3") (pintype "passive"))
    )
    (net (code "84") (name "SDA1") (class "Default")
      (node (ref "LPC1") (pin "57") (pinfunction "57_57") (pintype "passive"))
      (node (ref "X7") (pin "5") (pinfunction "S_5") (pintype "passive"))
    )
    (net (code "85") (name "SDA2") (class "Default")
      (node (ref "LPC1") (pin "40") (pinfunction "40_40") (pintype "passive"))
      (node (ref "R2") (pin "2") (pinfunction "2_2") (pintype "passive"))
      (node (ref "X6") (pin "5") (pinfunction "S_5") (pintype "passive"))
    )
    (net (code "86") (name "USB_DM") (class "Default")
      (node (ref "R3") (pin "2") (pinfunction "2_2") (pintype "passive"))
      (node (ref "X6") (pin "11") (pinfunction "S_11") (pintype "passive"))
    )
    (net (code "87") (name "USB_DP") (class "Default")
      (node (ref "R4") (pin "2") (pinfunction "2_2") (pintype "passive"))
      (node (ref "X6") (pin "13") (pinfunction "S_13") (pintype "passive"))
    )
    (net (code "88") (name "VCC") (class "Default")
      (node (ref "C1") (pin "+") (pinfunction "+_+") (pintype "passive"))
      (node (ref "C3") (pin "1") (pinfunction "1_1") (pintype "passive"))
      (node (ref "IC1") (pin "3") (pinfunction "VI_3") (pintype "input"))
      (node (ref "LPC1") (pin "2") (pinfunction "2_2") (pintype "passive"))
      (node (ref "R1") (pin "1") (pinfunction "1_1") (pintype "passive"))
      (node (ref "R2") (pin "1") (pinfunction "1_1") (pintype "passive"))
      (node (ref "X6") (pin "1") (pinfunction "S_1") (pintype "passive"))
      (node (ref "X7") (pin "1") (pinfunction "S_1") (pintype "passive"))
    )
    (net (code "89") (name "V_H") (class "Default")
      (node (ref "U1") (pin "10") (pinfunction "COM_10") (pintype "output"))
      (node (ref "U2") (pin "10") (pinfunction "COM_10") (pintype "output"))
      (node (ref "U3") (pin "10") (pinfunction "COM_10") (pintype "output"))
      (node (ref "U4") (pin "10") (pinfunction "COM_10") (pintype "output"))
      (node (ref "U5") (pin "10") (pinfunction "COM_10") (pintype "output"))
      (node (ref "X4") (pin "1") (pinfunction "KL_1") (pintype "passive"))
    )
    (net (code "90") (name "unconnected-(LPC1-Pad3)") (class "Default")
      (node (ref "LPC1") (pin "3") (pinfunction "3_3") (pintype "passive"))
    )
    (net (code "91") (name "unconnected-(LPC1-Pad4)") (class "Default")
      (node (ref "LPC1") (pin "4") (pinfunction "4_4") (pintype "passive"))
    )
    (net (code "92") (name "unconnected-(LPC1-Pad21)") (class "Default")
      (node (ref "LPC1") (pin "21") (pinfunction "21_21") (pintype "passive"))
    )
    (net (code "93") (name "unconnected-(LPC1-Pad22)") (class "Default")
      (node (ref "LPC1") (pin "22") (pinfunction "22_22") (pintype "passive"))
    )
    (net (code "94") (name "unconnected-(LPC1-Pad23)") (class "Default")
      (node (ref "LPC1") (pin "23") (pinfunction "23_23") (pintype "passive"))
    )
    (net (code "95") (name "unconnected-(LPC1-Pad24)") (class "Default")
      (node (ref "LPC1") (pin "24") (pinfunction "24_24") (pintype "passive"))
    )
    (net (code "96") (name "unconnected-(LPC1-Pad25)") (class "Default")
      (node (ref "LPC1") (pin "25") (pinfunction "25_25") (pintype "passive"))
    )
    (net (code "97") (name "unconnected-(LPC1-Pad26)") (class "Default")
      (node (ref "LPC1") (pin "26") (pinfunction "26_26") (pintype "passive"))
    )
    (net (code "98") (name "unconnected-(LPC1-Pad27)") (class "Default")
      (node (ref "LPC1") (pin "27") (pinfunction "27_27") (pintype "passive"))
    )
    (net (code "99") (name "unconnected-(LPC1-Pad29)") (class "Default")
      (node (ref "LPC1") (pin "29") (pinfunction "29_29") (pintype "passive"))
    )
    (net (code "100") (name "unconnected-(LPC1-Pad30)") (class "Default")
      (node (ref "LPC1") (pin "30") (pinfunction "30_30") (pintype "passive"))
    )
    (net (code "101") (name "unconnected-(LPC1-Pad31)") (class "Default")
      (node (ref "LPC1") (pin "31") (pinfunction "31_31") (pintype "passive"))
    )
    (net (code "102") (name "unconnected-(LPC1-Pad32)") (class "Default")
      (node (ref "LPC1") (pin "32") (pinfunction "32_32") (pintype "passive"))
    )
    (net (code "103") (name "unconnected-(LPC1-Pad33)") (class "Default")
      (node (ref "LPC1") (pin "33") (pinfunction "33_33") (pintype "passive"))
    )
    (net (code "104") (name "unconnected-(LPC1-Pad34)") (class "Default")
      (node (ref "LPC1") (pin "34") (pinfunction "34_34") (pintype "passive"))
    )
    (net (code "105") (name "unconnected-(LPC1-Pad35)") (class "Default")
      (node (ref "LPC1") (pin "35") (pinfunction "35_35") (pintype "passive"))
    )
    (net (code "106") (name "unconnected-(LPC1-Pad51)") (class "Default")
      (node (ref "LPC1") (pin "51") (pinfunction "51_51") (pintype "passive"))
    )
    (net (code "107") (name "unconnected-(LPC1-Pad54)") (class "Default")
      (node (ref "LPC1") (pin "54") (pinfunction "54_54") (pintype "passive"))
    )
    (net (code "108") (name "unconnected-(LPC1-Pad59)") (class "Default")
      (node (ref "LPC1") (pin "59") (pinfunction "59_59") (pintype "passive"))
    )
    (net (code "109") (name "unconnected-(LPC1-Pad60)") (class "Default")
      (node (ref "LPC1") (pin "60") (pinfunction "60_60") (pintype "passive"))
    )
    (net (code "110") (name "unconnected-(LPC1-Pad62)") (class "Default")
      (node (ref "LPC1") (pin "62") (pinfunction "62_62") (pintype "passive"))
    )
    (net (code "111") (name "unconnected-(LPC1-Pad63)") (class "Default")
      (node (ref "LPC1") (pin "63") (pinfunction "63_63") (pintype "passive"))
    )
    (net (code "112") (name "unconnected-(LPC1-Pad65)") (class "Default")
      (node (ref "LPC1") (pin "65") (pinfunction "65_65") (pintype "passive"))
    )
    (net (code "113") (name "unconnected-(LPC1-Pad66)") (class "Default")
      (node (ref "LPC1") (pin "66") (pinfunction "66_66") (pintype "passive"))
    )
    (net (code "114") (name "unconnected-(LPC1-Pad68)") (class "Default")
      (node (ref "LPC1") (pin "68") (pinfunction "68_68") (pintype "passive"))
    )
    (net (code "115") (name "unconnected-(LPC1-Pad69)") (class "Default")
      (node (ref "LPC1") (pin "69") (pinfunction "69_69") (pintype "passive"))
    )
    (net (code "116") (name "unconnected-(LPC1-Pad70)") (class "Default")
      (node (ref "LPC1") (pin "70") (pinfunction "70_70") (pintype "passive"))
    )
    (net (code "117") (name "unconnected-(X6N-S-Pad7)") (class "Default")
      (node (ref "X6") (pin "7") (pinfunction "S_7") (pintype "passive"))
    )
    (net (code "118") (name "unconnected-(X6P-S-Pad9)") (class "Default")
      (node (ref "X6") (pin "9") (pinfunction "S_9") (pintype "passive"))
    )
    (net (code "119") (name "unconnected-(X7C-S-Pad11)") (class "Default")
      (node (ref "X7") (pin "11") (pinfunction "S_11") (pintype "passive"))
    )
    (net (code "120") (name "unconnected-(X7D-S-Pad12)") (class "Default")
      (node (ref "X7") (pin "12") (pinfunction "S_12") (pintype "passive"))
    )
    (net (code "121") (name "unconnected-(X7E-S-Pad13)") (class "Default")
      (node (ref "X7") (pin "13") (pinfunction "S_13") (pintype "passive"))
    )
    (net (code "122") (name "unconnected-(X7F-S-Pad14)") (class "Default")
      (node (ref "X7") (pin "14") (pinfunction "S_14") (pintype "passive"))
    )
    (net (code "123") (name "unconnected-(X7H-S-Pad16)") (class "Default")
      (node (ref "X7") (pin "16") (pinfunction "S_16") (pintype "passive"))
    )
    (net (code "124") (name "unconnected-(X7N-S-Pad7)") (class "Default")
      (node (ref "X7") (pin "7") (pinfunction "S_7") (pintype "passive"))
    )
    (net (code "125") (name "unconnected-(X7P-S-Pad9)") (class "Default")
      (node (ref "X7") (pin "9") (pinfunction "S_9") (pintype "passive"))
    )
  )
)
